# Ahoura_Blinky.net
KiCad netlist of a schematic drawn in EAGLE
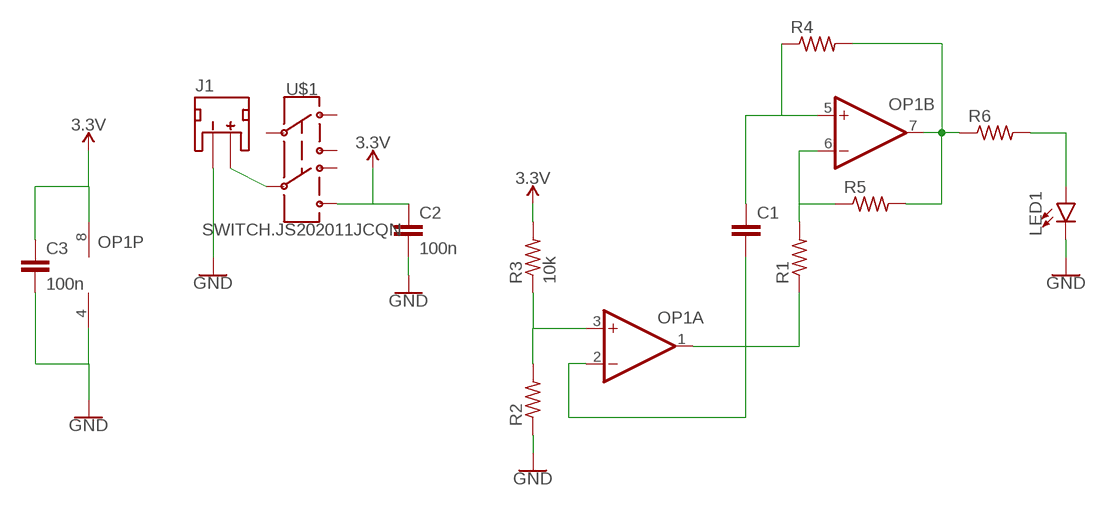
[diagram p0: schematic, sheet 1]

(export (version "E")
  (design (tool "Eeschema 10.0.6"))
  (components
    (comp (ref "C1")
      (value "CAPACITOR0402")
      (footprint "eagle-import:C0402")
      (libsource (lib "eagle-import") (part "CAPACITOR0402"))
    )
    (comp (ref "C2")
      (value "100n")
      (footprint "eagle-import:C0402")
      (libsource (lib "eagle-import") (part "CAPACITOR0402"))
    )
    (comp (ref "C3")
      (value "100n")
      (footprint "eagle-import:C0402")
      (libsource (lib "eagle-import") (part "CAPACITOR0402"))
    )
    (comp (ref "J1")
      (value "JST_2MM_MALE")
      (footprint "eagle-import:JST-2-SMD")
      (libsource (lib "eagle-import") (part "JST_2MM_MALE"))
    )
    (comp (ref "LED1")
      (value "LED0603")
      (footprint "eagle-import:LED-0603")
      (libsource (lib "eagle-import") (part "LED0603"))
    )
    (comp (ref "OP1")
      (value "OP-DUALRM")
      (footprint "eagle-import:MSOP08")
      (fields (field (name "MF") "ALTERA CORPORATION") (field (name "MPN") "AD8607ARMZ-REEL"))
      (libsource (lib "eagle-import") (part "OP-DUALRM"))
    )
    (comp (ref "R1")
      (value "RESISTOR0402")
      (footprint "eagle-import:R0402")
      (libsource (lib "eagle-import") (part "RESISTOR0402"))
    )
    (comp (ref "R2")
      (value "RESISTOR0402")
      (footprint "eagle-import:R0402")
      (libsource (lib "eagle-import") (part "RESISTOR0402"))
    )
    (comp (ref "R3")
      (value "10k")
      (footprint "eagle-import:R0402")
      (libsource (lib "eagle-import") (part "RESISTOR0402"))
    )
    (comp (ref "R4")
      (value "RESISTOR0402")
      (footprint "eagle-import:R0402")
      (libsource (lib "eagle-import") (part "RESISTOR0402"))
    )
    (comp (ref "R5")
      (value "RESISTOR0402")
      (footprint "eagle-import:R0402")
      (libsource (lib "eagle-import") (part "RESISTOR0402"))
    )
    (comp (ref "R6")
      (value "RESISTOR0402")
      (footprint "eagle-import:R0402")
      (libsource (lib "eagle-import") (part "RESISTOR0402"))
    )
    (comp (ref "U$1")
      (value "SWITCH.JS202011JCQN")
      (footprint "eagle-import:SWITCH.00")
      (libsource (lib "eagle-import") (part "SWITCH.JS202011JCQN"))
    )
  )
  (nets
    (net (code "1") (name "3.3V") (class "Default")
      (node (ref "C2") (pin "1") (pinfunction "1_1") (pintype "passive"))
      (node (ref "C3") (pin "1") (pinfunction "1_1") (pintype "passive"))
      (node (ref "OP1") (pin "8") (pinfunction "V+_8") (pintype "power_in"))
      (node (ref "R3") (pin "2") (pinfunction "2_2") (pintype "passive"))
      (node (ref "U$1") (pin "7") (pinfunction "7_7") (pintype "bidirectional"))
    )
    (net (code "2") (name "GND") (class "Default")
      (node (ref "C2") (pin "2") (pinfunction "2_2") (pintype "passive"))
      (node (ref "C3") (pin "2") (pinfunction "2_2") (pintype "passive"))
      (node (ref "J1") (pin "1") (pinfunction "-_1") (pintype "bidirectional"))
      (node (ref "LED1") (pin "C") (pinfunction "C_C") (pintype "passive"))
      (node (ref "OP1") (pin "4") (pinfunction "V-_4") (pintype "power_in"))
      (node (ref "R2") (pin "1") (pinfunction "1_1") (pintype "passive"))
    )
    (net (code "3") (name "Net-(J1-+)") (class "Default")
      (node (ref "J1") (pin "2") (pinfunction "+_2") (pintype "bidirectional"))
      (node (ref "U$1") (pin "6") (pinfunction "6_6") (pintype "bidirectional"))
    )
    (net (code "4") (name "Net-(LED1-PadA)") (class "Default")
      (node (ref "LED1") (pin "A") (pinfunction "A_A") (pintype "passive"))
      (node (ref "R6") (pin "2") (pinfunction "2_2") (pintype "passive"))
    )
    (net (code "5") (name "Net-(OP1A-+IN)") (class "Default")
      (node (ref "OP1") (pin "3") (pinfunction "+IN_3") (pintype "input"))
      (node (ref "R2") (pin "2") (pinfunction "2_2") (pintype "passive"))
      (node (ref "R3") (pin "1") (pinfunction "1_1") (pintype "passive"))
    )
    (net (code "6") (name "Net-(OP1A--IN)") (class "Default")
      (node (ref "C1") (pin "2") (pinfunction "2_2") (pintype "passive"))
      (node (ref "OP1") (pin "1") (pinfunction "OUT_1") (pintype "output"))
      (node (ref "OP1") (pin "2") (pinfunction "-IN_2") (pintype "input"))
      (node (ref "R1") (pin "1") (pinfunction "1_1") (pintype "passive"))
    )
    (net (code "7") (name "Net-(OP1B-+IN)") (class "Default")
      (node (ref "C1") (pin "1") (pinfunction "1_1") (pintype "passive"))
      (node (ref "OP1") (pin "5") (pinfunction "+IN_5") (pintype "input"))
      (node (ref "R4") (pin "1") (pinfunction "1_1") (pintype "passive"))
    )
    (net (code "8") (name "Net-(OP1B--IN)") (class "Default")
      (node (ref "OP1") (pin "6") (pinfunction "-IN_6") (pintype "input"))
      (node (ref "R1") (pin "2") (pinfunction "2_2") (pintype "passive"))
      (node (ref "R5") (pin "1") (pinfunction "1_1") (pintype "passive"))
    )
    (net (code "9") (name "Net-(OP1B-OUT)") (class "Default")
      (node (ref "OP1") (pin "7") (pinfunction "OUT_7") (pintype "output"))
      (node (ref "R4") (pin "2") (pinfunction "2_2") (pintype "passive"))
      (node (ref "R5") (pin "2") (pinfunction "2_2") (pintype "passive"))
      (node (ref "R6") (pin "1") (pinfunction "1_1") (pintype "passive"))
    )
    (net (code "10") (name "unconnected-(J1-PAD1-PadNC1)") (class "Default")
      (node (ref "J1") (pin "NC1") (pinfunction "PAD1_NC1") (pintype "bidirectional"))
    )
    (net (code "11") (name "unconnected-(J1-PAD2-PadNC2)") (class "Default")
      (node (ref "J1") (pin "NC2") (pinfunction "PAD2_NC2") (pintype "bidirectional"))
    )
    (net (code "12") (name "unconnected-(U$1-Pad1)") (class "Default")
      (node (ref "U$1") (pin "1") (pinfunction "1_1") (pintype "bidirectional"))
    )
    (net (code "13") (name "unconnected-(U$1-Pad2)") (class "Default")
      (node (ref "U$1") (pin "2") (pinfunction "2_2") (pintype "bidirectional"))
    )
    (net (code "14") (name "unconnected-(U$1-Pad3)") (class "Default")
      (node (ref "U$1") (pin "3") (pinfunction "3_3") (pintype "bidirectional"))
    )
    (net (code "15") (name "unconnected-(U$1-Pad5)") (class "Default")
      (node (ref "U$1") (pin "5") (pinfunction "5_5") (pintype "bidirectional"))
    )
  )
)
